# MCU.net
KiCad netlist of a schematic drawn in Altium Designer
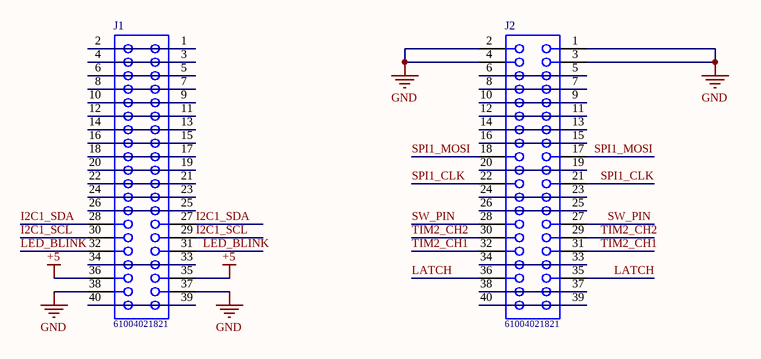
[diagram p0: MCU.SchDoc]

(export (version "E")
  (design (tool "Eeschema 10.0.6"))
  (components
    (comp (ref "J1")
      (value "61004021821")
      (footprint "61004021821")
      (description "WR-PHD Socket Header, SMT, pitch 2.54mm, Dual Row, Vertical, 40p")
      (fields (field (name "MANUFACTURER") "Wurth Elektronik"))
      (libsource (lib "Altium_WR-PHD (rev20a)") (part "61004021821"))
    )
    (comp (ref "J2")
      (value "61004021821")
      (footprint "61004021821")
      (description "WR-PHD Socket Header, SMT, pitch 2.54mm, Dual Row, Vertical, 40p")
      (fields (field (name "MANUFACTURER") "Wurth Elektronik"))
      (libsource (lib "Altium_WR-PHD (rev20a)") (part "61004021821"))
    )
  )
  (nets
    (net (code "1") (name "+5") (class "Default")
      (node (ref "J1") (pin "35") (pinfunction "35_35") (pintype "passive"))
      (node (ref "J1") (pin "36") (pinfunction "36_36") (pintype "passive"))
    )
    (net (code "2") (name "/I2C1_SCL") (class "Default")
      (node (ref "J1") (pin "29") (pinfunction "29_29") (pintype "passive"))
      (node (ref "J1") (pin "30") (pinfunction "30_30") (pintype "passive"))
    )
    (net (code "3") (name "/I2C1_SDA") (class "Default")
      (node (ref "J1") (pin "27") (pinfunction "27_27") (pintype "passive"))
      (node (ref "J1") (pin "28") (pinfunction "28_28") (pintype "passive"))
    )
    (net (code "4") (name "/LATCH") (class "Default")
      (node (ref "J2") (pin "35") (pinfunction "35_35") (pintype "passive"))
      (node (ref "J2") (pin "36") (pinfunction "36_36") (pintype "passive"))
    )
    (net (code "5") (name "/LED_BLINK") (class "Default")
      (node (ref "J1") (pin "31") (pinfunction "31_31") (pintype "passive"))
      (node (ref "J1") (pin "32") (pinfunction "32_32") (pintype "passive"))
    )
    (net (code "6") (name "/SPI1_CLK") (class "Default")
      (node (ref "J2") (pin "21") (pinfunction "21_21") (pintype "passive"))
      (node (ref "J2") (pin "22") (pinfunction "22_22") (pintype "passive"))
    )
    (net (code "7") (name "/SPI1_MOSI") (class "Default")
      (node (ref "J2") (pin "17") (pinfunction "17_17") (pintype "passive"))
      (node (ref "J2") (pin "18") (pinfunction "18_18") (pintype "passive"))
    )
    (net (code "8") (name "/SW_PIN") (class "Default")
      (node (ref "J2") (pin "27") (pinfunction "27_27") (pintype "passive"))
      (node (ref "J2") (pin "28") (pinfunction "28_28") (pintype "passive"))
    )
    (net (code "9") (name "/TIM2_CH1") (class "Default")
      (node (ref "J2") (pin "31") (pinfunction "31_31") (pintype "passive"))
      (node (ref "J2") (pin "32") (pinfunction "32_32") (pintype "passive"))
    )
    (net (code "10") (name "/TIM2_CH2") (class "Default")
      (node (ref "J2") (pin "29") (pinfunction "29_29") (pintype "passive"))
      (node (ref "J2") (pin "30") (pinfunction "30_30") (pintype "passive"))
    )
    (net (code "11") (name "GND") (class "Default")
      (node (ref "J1") (pin "37") (pinfunction "37_37") (pintype "passive"))
      (node (ref "J1") (pin "38") (pinfunction "38_38") (pintype "passive"))
      (node (ref "J2") (pin "1") (pinfunction "1_1") (pintype "passive"))
      (node (ref "J2") (pin "2") (pinfunction "2_2") (pintype "passive"))
      (node (ref "J2") (pin "3") (pinfunction "3_3") (pintype "passive"))
      (node (ref "J2") (pin "4") (pinfunction "4_4") (pintype "passive"))
    )
    (net (code "12") (name "Net-(J1-Pad1)") (class "Default")
      (node (ref "J1") (pin "1") (pinfunction "1_1") (pintype "passive"))
      (node (ref "J1") (pin "2") (pinfunction "2_2") (pintype "passive"))
    )
    (net (code "13") (name "Net-(J1-Pad3)") (class "Default")
      (node (ref "J1") (pin "3") (pinfunction "3_3") (pintype "passive"))
      (node (ref "J1") (pin "4") (pinfunction "4_4") (pintype "passive"))
    )
    (net (code "14") (name "Net-(J1-Pad5)") (class "Default")
      (node (ref "J1") (pin "5") (pinfunction "5_5") (pintype "passive"))
      (node (ref "J1") (pin "6") (pinfunction "6_6") (pintype "passive"))
    )
    (net (code "15") (name "Net-(J1-Pad7)") (class "Default")
      (node (ref "J1") (pin "7") (pinfunction "7_7") (pintype "passive"))
      (node (ref "J1") (pin "8") (pinfunction "8_8") (pintype "passive"))
    )
    (net (code "16") (name "Net-(J1-Pad10)") (class "Default")
      (node (ref "J1") (pin "10") (pinfunction "10_10") (pintype "passive"))
      (node (ref "J1") (pin "9") (pinfunction "9_9") (pintype "passive"))
    )
    (net (code "17") (name "Net-(J1-Pad11)") (class "Default")
      (node (ref "J1") (pin "11") (pinfunction "11_11") (pintype "passive"))
      (node (ref "J1") (pin "12") (pinfunction "12_12") (pintype "passive"))
    )
    (net (code "18") (name "Net-(J1-Pad13)") (class "Default")
      (node (ref "J1") (pin "13") (pinfunction "13_13") (pintype "passive"))
      (node (ref "J1") (pin "14") (pinfunction "14_14") (pintype "passive"))
    )
    (net (code "19") (name "Net-(J1-Pad15)") (class "Default")
      (node (ref "J1") (pin "15") (pinfunction "15_15") (pintype "passive"))
      (node (ref "J1") (pin "16") (pinfunction "16_16") (pintype "passive"))
    )
    (net (code "20") (name "Net-(J1-Pad17)") (class "Default")
      (node (ref "J1") (pin "17") (pinfunction "17_17") (pintype "passive"))
      (node (ref "J1") (pin "18") (pinfunction "18_18") (pintype "passive"))
    )
    (net (code "21") (name "Net-(J1-Pad19)") (class "Default")
      (node (ref "J1") (pin "19") (pinfunction "19_19") (pintype "passive"))
      (node (ref "J1") (pin "20") (pinfunction "20_20") (pintype "passive"))
    )
    (net (code "22") (name "Net-(J1-Pad21)") (class "Default")
      (node (ref "J1") (pin "21") (pinfunction "21_21") (pintype "passive"))
      (node (ref "J1") (pin "22") (pinfunction "22_22") (pintype "passive"))
    )
    (net (code "23") (name "Net-(J1-Pad23)") (class "Default")
      (node (ref "J1") (pin "23") (pinfunction "23_23") (pintype "passive"))
      (node (ref "J1") (pin "24") (pinfunction "24_24") (pintype "passive"))
    )
    (net (code "24") (name "Net-(J1-Pad25)") (class "Default")
      (node (ref "J1") (pin "25") (pinfunction "25_25") (pintype "passive"))
      (node (ref "J1") (pin "26") (pinfunction "26_26") (pintype "passive"))
    )
    (net (code "25") (name "Net-(J1-Pad33)") (class "Default")
      (node (ref "J1") (pin "33") (pinfunction "33_33") (pintype "passive"))
      (node (ref "J1") (pin "34") (pinfunction "34_34") (pintype "passive"))
    )
    (net (code "26") (name "Net-(J1-Pad39)") (class "Default")
      (node (ref "J1") (pin "39") (pinfunction "39_39") (pintype "passive"))
      (node (ref "J1") (pin "40") (pinfunction "40_40") (pintype "passive"))
    )
    (net (code "27") (name "Net-(J2-Pad5)") (class "Default")
      (node (ref "J2") (pin "5") (pinfunction "5_5") (pintype "passive"))
      (node (ref "J2") (pin "6") (pinfunction "6_6") (pintype "passive"))
    )
    (net (code "28") (name "Net-(J2-Pad7)") (class "Default")
      (node (ref "J2") (pin "7") (pinfunction "7_7") (pintype "passive"))
      (node (ref "J2") (pin "8") (pinfunction "8_8") (pintype "passive"))
    )
    (net (code "29") (name "Net-(J2-Pad10)") (class "Default")
      (node (ref "J2") (pin "10") (pinfunction "10_10") (pintype "passive"))
      (node (ref "J2") (pin "9") (pinfunction "9_9") (pintype "passive"))
    )
    (net (code "30") (name "Net-(J2-Pad11)") (class "Default")
      (node (ref "J2") (pin "11") (pinfunction "11_11") (pintype "passive"))
      (node (ref "J2") (pin "12") (pinfunction "12_12") (pintype "passive"))
    )
    (net (code "31") (name "Net-(J2-Pad13)") (class "Default")
      (node (ref "J2") (pin "13") (pinfunction "13_13") (pintype "passive"))
      (node (ref "J2") (pin "14") (pinfunction "14_14") (pintype "passive"))
    )
    (net (code "32") (name "Net-(J2-Pad15)") (class "Default")
      (node (ref "J2") (pin "15") (pinfunction "15_15") (pintype "passive"))
      (node (ref "J2") (pin "16") (pinfunction "16_16") (pintype "passive"))
    )
    (net (code "33") (name "Net-(J2-Pad19)") (class "Default")
      (node (ref "J2") (pin "19") (pinfunction "19_19") (pintype "passive"))
      (node (ref "J2") (pin "20") (pinfunction "20_20") (pintype "passive"))
    )
    (net (code "34") (name "Net-(J2-Pad23)") (class "Default")
      (node (ref "J2") (pin "23") (pinfunction "23_23") (pintype "passive"))
      (node (ref "J2") (pin "24") (pinfunction "24_24") (pintype "passive"))
    )
    (net (code "35") (name "Net-(J2-Pad25)") (class "Default")
      (node (ref "J2") (pin "25") (pinfunction "25_25") (pintype "passive"))
      (node (ref "J2") (pin "26") (pinfunction "26_26") (pintype "passive"))
    )
    (net (code "36") (name "Net-(J2-Pad33)") (class "Default")
      (node (ref "J2") (pin "33") (pinfunction "33_33") (pintype "passive"))
      (node (ref "J2") (pin "34") (pinfunction "34_34") (pintype "passive"))
    )
    (net (code "37") (name "Net-(J2-Pad37)") (class "Default")
      (node (ref "J2") (pin "37") (pinfunction "37_37") (pintype "passive"))
      (node (ref "J2") (pin "38") (pinfunction "38_38") (pintype "passive"))
    )
    (net (code "38") (name "Net-(J2-Pad39)") (class "Default")
      (node (ref "J2") (pin "39") (pinfunction "39_39") (pintype "passive"))
      (node (ref "J2") (pin "40") (pinfunction "40_40") (pintype "passive"))
    )
  )
)
